# 3-Power_Peripherals.net
KiCad netlist of a schematic drawn in Altium Designer
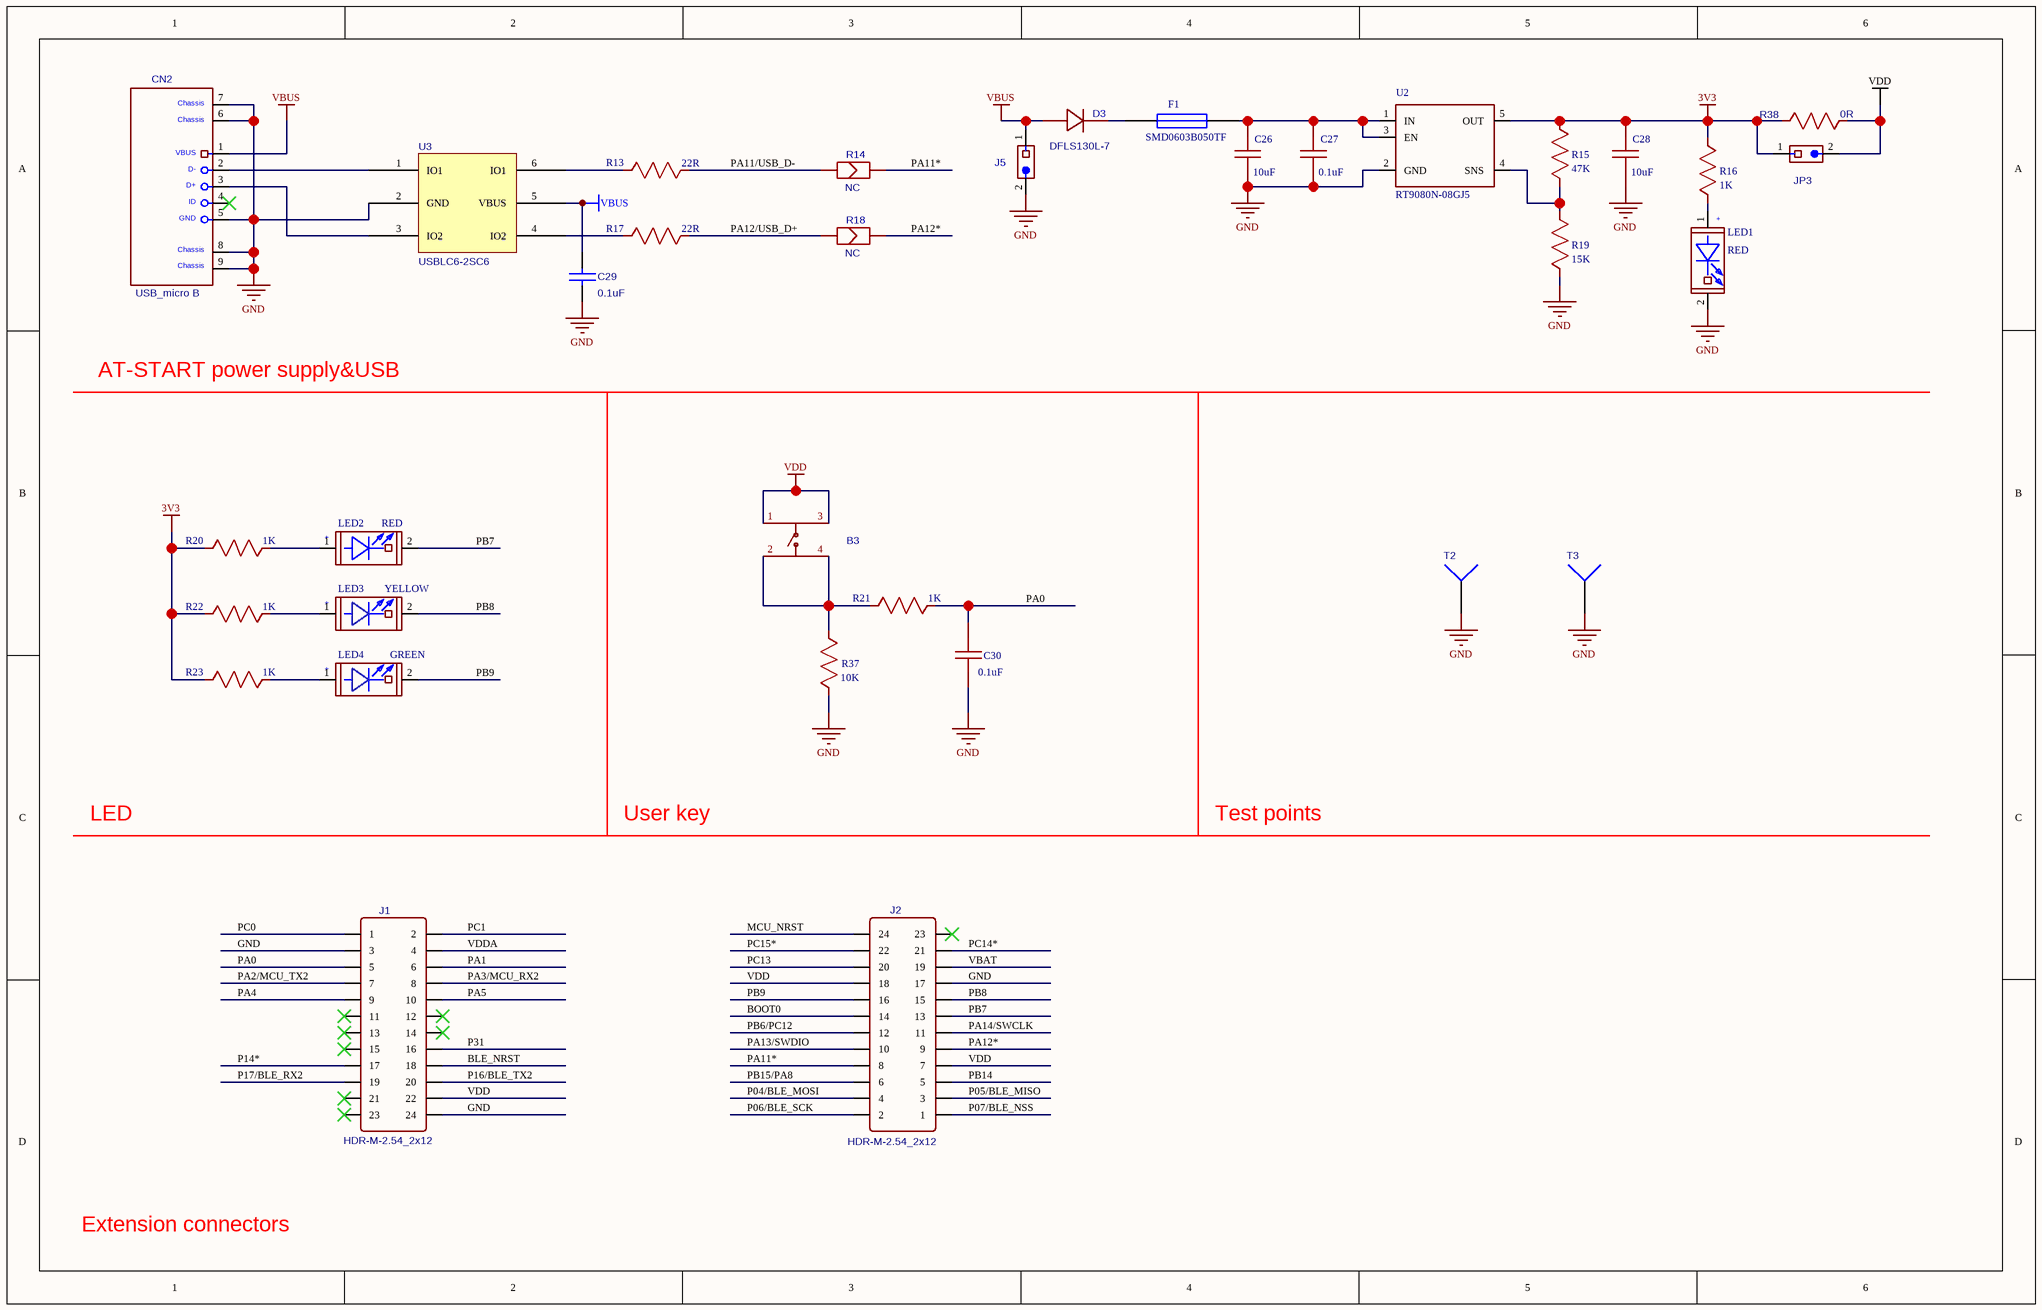
[diagram p0: 3-Power&Peripherals.schdoc]

(export (version "E")
  (design (tool "Eeschema 10.0.6"))
  (components
    (comp (ref "B3")
      (value "贴片按键6*6*5 蓝色")
      (fields
        (field (name "BOM_SUPPLIER PART") "C707347")
        (field (name "BOM_MANUFACTURER PART") "K2-1102SP-C3SC-04")
        (field (name "CONTRIBUTOR") "LCSC")
      )
      (libsource (lib "altium-import") (part "root_0_贴片按键6*6*5 蓝色_"))
    )
    (comp (ref "C26")
      (value "10uF")
      (fields (field (name "CONTRIBUTOR") "LCEDA_Lib"))
      (libsource (lib "altium-import") (part "root_3_10uF_"))
    )
    (comp (ref "C27")
      (value "0.1uF")
      (fields (field (name "CONTRIBUTOR") "LCEDA_Lib"))
      (libsource (lib "altium-import") (part "root_3_0.1uF_"))
    )
    (comp (ref "C28")
      (value "10uF")
      (fields (field (name "CONTRIBUTOR") "LCEDA_Lib"))
      (libsource (lib "altium-import") (part "root_3_10uF_"))
    )
    (comp (ref "C29") (value "0.1uF") (libsource (lib "altium-import") (part "root_1_0.1uF_")))
    (comp (ref "C30")
      (value "0.1uF")
      (fields (field (name "CONTRIBUTOR") "LCEDA_Lib"))
      (libsource (lib "") (part "root_1_0.1uF__1"))
    )
    (comp (ref "CN2") (value "USB_micro B") (libsource (lib "altium-import") (part "root_0_USB_micro B_")))
    (comp (ref "D3")
      (value "DFLS130L-7")
      (fields (field (name "BOM_SUPPLIER PART") "C110493") (field (name "CONTRIBUTOR") "LCSC"))
      (libsource (lib "altium-import") (part "root_0_DFLS130L-7_"))
    )
    (comp (ref "F1")
      (value "SMD0603B050TF")
      (fields (field (name "PUBLISHER") "Altium Limited"))
      (libsource (lib "altium-import") (part "root_0_SMD0603B050TF_"))
    )
    (comp (ref "J1")
      (value "HDR-M-2.54_2x12")
      (fields (field (name "CONTRIBUTOR") "twb17"))
      (libsource (lib "altium-import") (part "root_0_HDR-M-2.54_2x12_"))
    )
    (comp (ref "J2")
      (value "HDR-M-2.54_2x12")
      (fields (field (name "CONTRIBUTOR") "twb17"))
      (libsource (lib "altium-import") (part "root_2_HDR-M-2.54_2x12_"))
    )
    (comp (ref "J5")
      (value "1X2P,Male,DIP_2.54")
      (fields (field (name "CONTRIBUTOR") "twb17"))
      (libsource (lib "altium-import") (part "root_1_1X2P,Male,DIP_2.54_"))
    )
    (comp (ref "JP3")
      (value "Jumper 1x2P")
      (fields (field (name "CONTRIBUTOR") "twb17"))
      (libsource (lib "altium-import") (part "root_0_Jumper 1x2P_"))
    )
    (comp (ref "LED1") (value "RED") (libsource (lib "altium-import") (part "root_3_RED_")))
    (comp (ref "LED2") (value "RED") (libsource (lib "altium-import") (part "root_0_RED_")))
    (comp (ref "LED3") (value "YELLOW") (libsource (lib "altium-import") (part "root_0_YELLOW_")))
    (comp (ref "LED4") (value "GREEN") (libsource (lib "altium-import") (part "root_0_GREEN_")))
    (comp (ref "R13")
      (value "22R")
      (fields (field (name "CONTRIBUTOR") "LCEDA_Lib"))
      (libsource (lib "altium-import") (part "root_2_22R_"))
    )
    (comp (ref "R14")
      (value "NC")
      (fields (field (name "CONTRIBUTOR") "twb17"))
      (libsource (lib "altium-import") (part "root_0_NC_"))
    )
    (comp (ref "R15")
      (value "47K")
      (fields (field (name "CONTRIBUTOR") "LCEDA_Lib"))
      (libsource (lib "altium-import") (part "root_1_47K_"))
    )
    (comp (ref "R16")
      (value "1K")
      (fields (field (name "CONTRIBUTOR") "LCEDA_Lib"))
      (libsource (lib "altium-import") (part "root_3_1K_"))
    )
    (comp (ref "R17")
      (value "22R")
      (fields (field (name "CONTRIBUTOR") "LCEDA_Lib"))
      (libsource (lib "altium-import") (part "root_2_22R_"))
    )
    (comp (ref "R18")
      (value "NC")
      (fields (field (name "CONTRIBUTOR") "twb17"))
      (libsource (lib "altium-import") (part "root_0_NC_"))
    )
    (comp (ref "R19")
      (value "15K")
      (fields (field (name "CONTRIBUTOR") "LCEDA_Lib"))
      (libsource (lib "altium-import") (part "root_1_15K_"))
    )
    (comp (ref "R20")
      (value "1K")
      (fields (field (name "CONTRIBUTOR") "LCEDA_Lib"))
      (libsource (lib "altium-import") (part "root_2_1K_"))
    )
    (comp (ref "R21")
      (value "1K")
      (fields (field (name "CONTRIBUTOR") "LCEDA_Lib"))
      (libsource (lib "altium-import") (part "root_2_1K_"))
    )
    (comp (ref "R22")
      (value "1K")
      (fields (field (name "CONTRIBUTOR") "LCEDA_Lib"))
      (libsource (lib "altium-import") (part "root_2_1K_"))
    )
    (comp (ref "R23")
      (value "1K")
      (fields (field (name "CONTRIBUTOR") "LCEDA_Lib"))
      (libsource (lib "altium-import") (part "root_2_1K_"))
    )
    (comp (ref "R37")
      (value "10K")
      (fields (field (name "CONTRIBUTOR") "LCEDA_Lib"))
      (libsource (lib "altium-import") (part "root_3_10K_"))
    )
    (comp (ref "R38")
      (value "0R")
      (fields (field (name "CONTRIBUTOR") "LCEDA_Lib"))
      (libsource (lib "altium-import") (part "root_0_0R_"))
    )
    (comp (ref "T2")
      (value "Testpoint")
      (fields (field (name "PUBLISHER") "Altium Limited"))
      (libsource (lib "altium-import") (part "root_3_Testpoint_"))
    )
    (comp (ref "T3")
      (value "Testpoint")
      (fields (field (name "PUBLISHER") "Altium Limited"))
      (libsource (lib "altium-import") (part "root_3_Testpoint_"))
    )
    (comp (ref "U2") (value "RT9080N-08GJ5") (libsource (lib "altium-import") (part "root_0_RT9080N-08GJ5_")))
    (comp (ref "U3") (value "USBLC6-2SC6") (libsource (lib "altium-import") (part "root_0_USBLC6-2SC6_")))
  )
  (nets
    (net (code "1") (name "/BLE_NRST") (class "Default")
      (node (ref "J1") (pin "18") (pinfunction "18_18") (pintype "passive"))
    )
    (net (code "2") (name "/BOOT0") (class "Default")
      (node (ref "J2") (pin "14") (pinfunction "14_14") (pintype "passive"))
    )
    (net (code "3") (name "/MCU_NRST") (class "Default")
      (node (ref "J2") (pin "24") (pinfunction "24_24") (pintype "passive"))
    )
    (net (code "4") (name "/P04{slash}BLE_MOSI") (class "Default")
      (node (ref "J2") (pin "4") (pinfunction "4_4") (pintype "passive"))
    )
    (net (code "5") (name "/P05{slash}BLE_MISO") (class "Default")
      (node (ref "J2") (pin "3") (pinfunction "3_3") (pintype "passive"))
    )
    (net (code "6") (name "/P06{slash}BLE_SCK") (class "Default")
      (node (ref "J2") (pin "2") (pinfunction "2_2") (pintype "passive"))
    )
    (net (code "7") (name "/P07{slash}BLE_NSS") (class "Default")
      (node (ref "J2") (pin "1") (pinfunction "1_1") (pintype "passive"))
    )
    (net (code "8") (name "/P14*") (class "Default")
      (node (ref "J1") (pin "17") (pinfunction "17_17") (pintype "passive"))
    )
    (net (code "9") (name "/P16{slash}BLE_TX2") (class "Default")
      (node (ref "J1") (pin "20") (pinfunction "20_20") (pintype "passive"))
    )
    (net (code "10") (name "/P17{slash}BLE_RX2") (class "Default")
      (node (ref "J1") (pin "19") (pinfunction "19_19") (pintype "passive"))
    )
    (net (code "11") (name "/P31") (class "Default")
      (node (ref "J1") (pin "16") (pinfunction "16_16") (pintype "passive"))
    )
    (net (code "12") (name "/PA0") (class "Default")
      (node (ref "C30") (pin "2") (pinfunction "2_2") (pintype "passive"))
      (node (ref "J1") (pin "5") (pinfunction "5_5") (pintype "passive"))
      (node (ref "R21") (pin "1") (pinfunction "1_1") (pintype "passive"))
    )
    (net (code "13") (name "/PA1") (class "Default")
      (node (ref "J1") (pin "6") (pinfunction "6_6") (pintype "passive"))
    )
    (net (code "14") (name "/PA2{slash}MCU_TX2") (class "Default")
      (node (ref "J1") (pin "7") (pinfunction "7_7") (pintype "passive"))
    )
    (net (code "15") (name "/PA3{slash}MCU_RX2") (class "Default")
      (node (ref "J1") (pin "8") (pinfunction "8_8") (pintype "passive"))
    )
    (net (code "16") (name "/PA4") (class "Default")
      (node (ref "J1") (pin "9") (pinfunction "9_9") (pintype "passive"))
    )
    (net (code "17") (name "/PA5") (class "Default")
      (node (ref "J1") (pin "10") (pinfunction "10_10") (pintype "passive"))
    )
    (net (code "18") (name "/PA11*") (class "Default")
      (node (ref "J2") (pin "8") (pinfunction "8_8") (pintype "passive"))
      (node (ref "R14") (pin "2") (pinfunction "2_2") (pintype "passive"))
    )
    (net (code "19") (name "/PA11{slash}USB_D-") (class "Default")
      (node (ref "R13") (pin "1") (pinfunction "1_1") (pintype "passive"))
      (node (ref "R14") (pin "1") (pinfunction "1_1") (pintype "passive"))
    )
    (net (code "20") (name "/PA12*") (class "Default")
      (node (ref "J2") (pin "9") (pinfunction "9_9") (pintype "passive"))
      (node (ref "R18") (pin "2") (pinfunction "2_2") (pintype "passive"))
    )
    (net (code "21") (name "/PA12{slash}USB_D+") (class "Default")
      (node (ref "R17") (pin "1") (pinfunction "1_1") (pintype "passive"))
      (node (ref "R18") (pin "1") (pinfunction "1_1") (pintype "passive"))
    )
    (net (code "22") (name "/PA13{slash}SWDIO") (class "Default")
      (node (ref "J2") (pin "10") (pinfunction "10_10") (pintype "passive"))
    )
    (net (code "23") (name "/PA14{slash}SWCLK") (class "Default")
      (node (ref "J2") (pin "11") (pinfunction "11_11") (pintype "passive"))
    )
    (net (code "24") (name "/PB6{slash}PC12") (class "Default")
      (node (ref "J2") (pin "12") (pinfunction "12_12") (pintype "passive"))
    )
    (net (code "25") (name "/PB7") (class "Default")
      (node (ref "J2") (pin "13") (pinfunction "13_13") (pintype "passive"))
      (node (ref "LED2") (pin "2") (pinfunction "CATHODE_2") (pintype "passive"))
    )
    (net (code "26") (name "/PB8") (class "Default")
      (node (ref "J2") (pin "15") (pinfunction "15_15") (pintype "passive"))
      (node (ref "LED3") (pin "2") (pinfunction "CATHODE_2") (pintype "passive"))
    )
    (net (code "27") (name "/PB9") (class "Default")
      (node (ref "J2") (pin "16") (pinfunction "16_16") (pintype "passive"))
      (node (ref "LED4") (pin "2") (pinfunction "CATHODE_2") (pintype "passive"))
    )
    (net (code "28") (name "/PB14") (class "Default")
      (node (ref "J2") (pin "5") (pinfunction "5_5") (pintype "passive"))
    )
    (net (code "29") (name "/PB15{slash}PA8") (class "Default")
      (node (ref "J2") (pin "6") (pinfunction "6_6") (pintype "passive"))
    )
    (net (code "30") (name "/PC0") (class "Default")
      (node (ref "J1") (pin "1") (pinfunction "1_1") (pintype "passive"))
    )
    (net (code "31") (name "/PC1") (class "Default")
      (node (ref "J1") (pin "2") (pinfunction "2_2") (pintype "passive"))
    )
    (net (code "32") (name "/PC13") (class "Default")
      (node (ref "J2") (pin "20") (pinfunction "20_20") (pintype "passive"))
    )
    (net (code "33") (name "/PC14*") (class "Default")
      (node (ref "J2") (pin "21") (pinfunction "21_21") (pintype "passive"))
    )
    (net (code "34") (name "/PC15*") (class "Default")
      (node (ref "J2") (pin "22") (pinfunction "22_22") (pintype "passive"))
    )
    (net (code "35") (name "/VBAT") (class "Default")
      (node (ref "J2") (pin "19") (pinfunction "19_19") (pintype "passive"))
    )
    (net (code "36") (name "/VDDA") (class "Default")
      (node (ref "J1") (pin "4") (pinfunction "4_4") (pintype "passive"))
    )
    (net (code "37") (name "3V3") (class "Default")
      (node (ref "C28") (pin "1") (pinfunction "1_1") (pintype "passive"))
      (node (ref "JP3") (pin "1") (pinfunction "1_1") (pintype "passive"))
      (node (ref "R15") (pin "2") (pinfunction "2_2") (pintype "passive"))
      (node (ref "R16") (pin "1") (pinfunction "1_1") (pintype "passive"))
      (node (ref "R20") (pin "2") (pinfunction "2_2") (pintype "passive"))
      (node (ref "R22") (pin "2") (pinfunction "2_2") (pintype "passive"))
      (node (ref "R23") (pin "2") (pinfunction "2_2") (pintype "passive"))
      (node (ref "R38") (pin "1") (pinfunction "1_1") (pintype "passive"))
      (node (ref "U2") (pin "5") (pinfunction "OUT_5") (pintype "passive"))
    )
    (net (code "38") (name "GND") (class "Default")
      (node (ref "C26") (pin "2") (pinfunction "2_2") (pintype "passive"))
      (node (ref "C27") (pin "2") (pinfunction "2_2") (pintype "passive"))
      (node (ref "C28") (pin "2") (pinfunction "2_2") (pintype "passive"))
      (node (ref "C29") (pin "1") (pinfunction "1_1") (pintype "passive"))
      (node (ref "C30") (pin "1") (pinfunction "1_1") (pintype "passive"))
      (node (ref "CN2") (pin "5") (pinfunction "GND_5") (pintype "passive"))
      (node (ref "CN2") (pin "6") (pinfunction "6_6") (pintype "passive"))
      (node (ref "CN2") (pin "7") (pinfunction "7_7") (pintype "passive"))
      (node (ref "CN2") (pin "8") (pinfunction "8_8") (pintype "passive"))
      (node (ref "CN2") (pin "9") (pinfunction "9_9") (pintype "passive"))
      (node (ref "J1") (pin "24") (pinfunction "24_24") (pintype "passive"))
      (node (ref "J1") (pin "3") (pinfunction "3_3") (pintype "passive"))
      (node (ref "J2") (pin "17") (pinfunction "17_17") (pintype "passive"))
      (node (ref "J5") (pin "2") (pinfunction "2_2") (pintype "passive"))
      (node (ref "LED1") (pin "2") (pinfunction "CATHODE_2") (pintype "passive"))
      (node (ref "R19") (pin "1") (pinfunction "1_1") (pintype "passive"))
      (node (ref "R37") (pin "2") (pinfunction "2_2") (pintype "passive"))
      (node (ref "T2") (pin "1") (pinfunction "1_1") (pintype "passive"))
      (node (ref "T3") (pin "1") (pinfunction "1_1") (pintype "passive"))
      (node (ref "U2") (pin "2") (pinfunction "GND_2") (pintype "passive"))
      (node (ref "U3") (pin "2") (pinfunction "GND_2") (pintype "passive"))
    )
    (net (code "39") (name "Net-(B3-Pad2)") (class "Default")
      (node (ref "B3") (pin "2") (pinfunction "2_2") (pintype "passive"))
      (node (ref "B3") (pin "4") (pinfunction "4_4") (pintype "passive"))
      (node (ref "R21") (pin "2") (pinfunction "2_2") (pintype "passive"))
      (node (ref "R37") (pin "1") (pinfunction "1_1") (pintype "passive"))
    )
    (net (code "40") (name "Net-(CN2-D+)") (class "Default")
      (node (ref "CN2") (pin "3") (pinfunction "D+_3") (pintype "passive"))
      (node (ref "U3") (pin "3") (pinfunction "IO2_3") (pintype "passive"))
    )
    (net (code "41") (name "Net-(CN2-D-)") (class "Default")
      (node (ref "CN2") (pin "2") (pinfunction "D-_2") (pintype "passive"))
      (node (ref "U3") (pin "1") (pinfunction "IO1_1") (pintype "passive"))
    )
    (net (code "42") (name "Net-(D3-Pad1)") (class "Default")
      (node (ref "D3") (pin "1") (pinfunction "1_1") (pintype "passive"))
      (node (ref "F1") (pin "1") (pinfunction "1_1") (pintype "passive"))
    )
    (net (code "43") (name "Net-(LED1-ANODE)") (class "Default")
      (node (ref "LED1") (pin "1") (pinfunction "ANODE_1") (pintype "passive"))
      (node (ref "R16") (pin "2") (pinfunction "2_2") (pintype "passive"))
    )
    (net (code "44") (name "Net-(LED2-ANODE)") (class "Default")
      (node (ref "LED2") (pin "1") (pinfunction "ANODE_1") (pintype "passive"))
      (node (ref "R20") (pin "1") (pinfunction "1_1") (pintype "passive"))
    )
    (net (code "45") (name "Net-(LED3-ANODE)") (class "Default")
      (node (ref "LED3") (pin "1") (pinfunction "ANODE_1") (pintype "passive"))
      (node (ref "R22") (pin "1") (pinfunction "1_1") (pintype "passive"))
    )
    (net (code "46") (name "Net-(LED4-ANODE)") (class "Default")
      (node (ref "LED4") (pin "1") (pinfunction "ANODE_1") (pintype "passive"))
      (node (ref "R23") (pin "1") (pinfunction "1_1") (pintype "passive"))
    )
    (net (code "47") (name "Net-(R13-Pad2)") (class "Default")
      (node (ref "R13") (pin "2") (pinfunction "2_2") (pintype "passive"))
      (node (ref "U3") (pin "6") (pinfunction "IO1_6") (pintype "passive"))
    )
    (net (code "48") (name "Net-(R17-Pad2)") (class "Default")
      (node (ref "R17") (pin "2") (pinfunction "2_2") (pintype "passive"))
      (node (ref "U3") (pin "4") (pinfunction "IO2_4") (pintype "passive"))
    )
    (net (code "49") (name "Net-(U2-EN)") (class "Default")
      (node (ref "C26") (pin "1") (pinfunction "1_1") (pintype "passive"))
      (node (ref "C27") (pin "1") (pinfunction "1_1") (pintype "passive"))
      (node (ref "F1") (pin "2") (pinfunction "2_2") (pintype "passive"))
      (node (ref "U2") (pin "1") (pinfunction "IN_1") (pintype "passive"))
      (node (ref "U2") (pin "3") (pinfunction "EN_3") (pintype "passive"))
    )
    (net (code "50") (name "Net-(U2-SNS)") (class "Default")
      (node (ref "R15") (pin "1") (pinfunction "1_1") (pintype "passive"))
      (node (ref "R19") (pin "2") (pinfunction "2_2") (pintype "passive"))
      (node (ref "U2") (pin "4") (pinfunction "SNS_4") (pintype "passive"))
    )
    (net (code "51") (name "VBUS") (class "Default")
      (node (ref "C29") (pin "2") (pinfunction "2_2") (pintype "passive"))
      (node (ref "CN2") (pin "1") (pinfunction "VBUS_1") (pintype "passive"))
      (node (ref "D3") (pin "2") (pinfunction "2_2") (pintype "passive"))
      (node (ref "J5") (pin "1") (pinfunction "1_1") (pintype "passive"))
      (node (ref "U3") (pin "5") (pinfunction "VBUS_5") (pintype "passive"))
    )
    (net (code "52") (name "VDD") (class "Default")
      (node (ref "B3") (pin "1") (pinfunction "1_1") (pintype "passive"))
      (node (ref "B3") (pin "3") (pinfunction "3_3") (pintype "passive"))
      (node (ref "J1") (pin "22") (pinfunction "22_22") (pintype "passive"))
      (node (ref "J2") (pin "18") (pinfunction "18_18") (pintype "passive"))
      (node (ref "J2") (pin "7") (pinfunction "7_7") (pintype "passive"))
      (node (ref "JP3") (pin "2") (pinfunction "2_2") (pintype "passive"))
      (node (ref "R38") (pin "2") (pinfunction "2_2") (pintype "passive"))
    )
    (net (code "53") (name "unconnected-(CN2-ID-Pad4)") (class "Default")
      (node (ref "CN2") (pin "4") (pinfunction "ID_4") (pintype "passive+no_connect"))
    )
    (net (code "54") (name "unconnected-(J1-Pad11)") (class "Default")
      (node (ref "J1") (pin "11") (pinfunction "11_11") (pintype "passive+no_connect"))
    )
    (net (code "55") (name "unconnected-(J1-Pad12)") (class "Default")
      (node (ref "J1") (pin "12") (pinfunction "12_12") (pintype "passive+no_connect"))
    )
    (net (code "56") (name "unconnected-(J1-Pad13)") (class "Default")
      (node (ref "J1") (pin "13") (pinfunction "13_13") (pintype "passive+no_connect"))
    )
    (net (code "57") (name "unconnected-(J1-Pad14)") (class "Default")
      (node (ref "J1") (pin "14") (pinfunction "14_14") (pintype "passive+no_connect"))
    )
    (net (code "58") (name "unconnected-(J1-Pad15)") (class "Default")
      (node (ref "J1") (pin "15") (pinfunction "15_15") (pintype "passive+no_connect"))
    )
    (net (code "59") (name "unconnected-(J1-Pad21)") (class "Default")
      (node (ref "J1") (pin "21") (pinfunction "21_21") (pintype "passive+no_connect"))
    )
    (net (code "60") (name "unconnected-(J1-Pad23)") (class "Default")
      (node (ref "J1") (pin "23") (pinfunction "23_23") (pintype "passive+no_connect"))
    )
    (net (code "61") (name "unconnected-(J2-Pad23)") (class "Default")
      (node (ref "J2") (pin "23") (pinfunction "23_23") (pintype "passive+no_connect"))
    )
  )
)
